# Led_Strip_8mm.net
KiCad netlist of a schematic drawn in Altium Designer
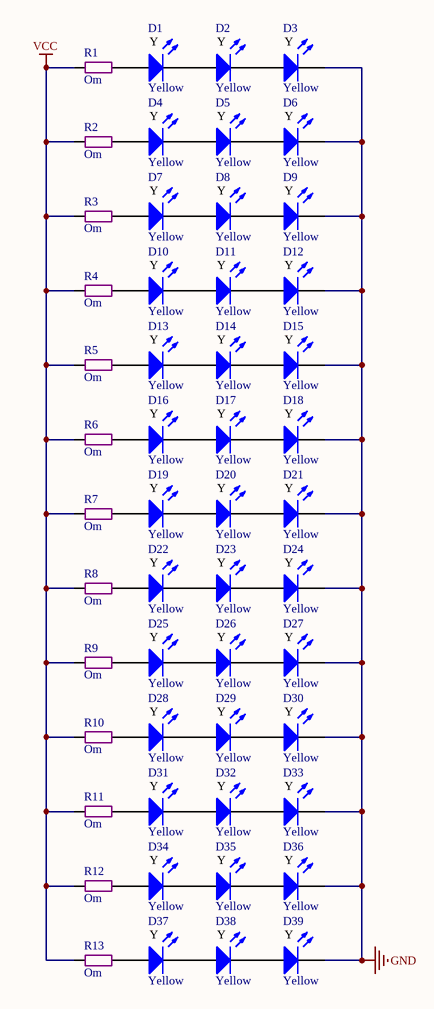
[diagram p0: Led Strip 8mm.SchDoc]

(export (version "E")
  (design (tool "Eeschema 10.0.6"))
  (components
    (comp (ref "D1")
      (value "Yellow")
      (footprint "LED:LED Round 8mm Yellow")
      (description "2.8-3v 25mA, 4-5cd")
      (libsource (lib "LED") (part "Led Round 8mm Yellow 0.5W"))
    )
    (comp (ref "D2")
      (value "Yellow")
      (footprint "LED:LED Round 8mm Yellow")
      (description "2.8-3v 25mA, 4-5cd")
      (libsource (lib "LED") (part "Led Round 8mm Yellow 0.5W"))
    )
    (comp (ref "D3")
      (value "Yellow")
      (footprint "LED:LED Round 8mm Yellow")
      (description "2.8-3v 25mA, 4-5cd")
      (libsource (lib "LED") (part "Led Round 8mm Yellow 0.5W"))
    )
    (comp (ref "D4")
      (value "Yellow")
      (footprint "LED:LED Round 8mm Yellow")
      (description "2.8-3v 25mA, 4-5cd")
      (libsource (lib "LED") (part "Led Round 8mm Yellow 0.5W"))
    )
    (comp (ref "D5")
      (value "Yellow")
      (footprint "LED:LED Round 8mm Yellow")
      (description "2.8-3v 25mA, 4-5cd")
      (libsource (lib "LED") (part "Led Round 8mm Yellow 0.5W"))
    )
    (comp (ref "D6")
      (value "Yellow")
      (footprint "LED:LED Round 8mm Yellow")
      (description "2.8-3v 25mA, 4-5cd")
      (libsource (lib "LED") (part "Led Round 8mm Yellow 0.5W"))
    )
    (comp (ref "D7")
      (value "Yellow")
      (footprint "LED:LED Round 8mm Yellow")
      (description "2.8-3v 25mA, 4-5cd")
      (libsource (lib "LED") (part "Led Round 8mm Yellow 0.5W"))
    )
    (comp (ref "D8")
      (value "Yellow")
      (footprint "LED:LED Round 8mm Yellow")
      (description "2.8-3v 25mA, 4-5cd")
      (libsource (lib "LED") (part "Led Round 8mm Yellow 0.5W"))
    )
    (comp (ref "D9")
      (value "Yellow")
      (footprint "LED:LED Round 8mm Yellow")
      (description "2.8-3v 25mA, 4-5cd")
      (libsource (lib "LED") (part "Led Round 8mm Yellow 0.5W"))
    )
    (comp (ref "D10")
      (value "Yellow")
      (footprint "LED:LED Round 8mm Yellow")
      (description "2.8-3v 25mA, 4-5cd")
      (libsource (lib "LED") (part "Led Round 8mm Yellow 0.5W"))
    )
    (comp (ref "D11")
      (value "Yellow")
      (footprint "LED:LED Round 8mm Yellow")
      (description "2.8-3v 25mA, 4-5cd")
      (libsource (lib "LED") (part "Led Round 8mm Yellow 0.5W"))
    )
    (comp (ref "D12")
      (value "Yellow")
      (footprint "LED:LED Round 8mm Yellow")
      (description "2.8-3v 25mA, 4-5cd")
      (libsource (lib "LED") (part "Led Round 8mm Yellow 0.5W"))
    )
    (comp (ref "D13")
      (value "Yellow")
      (footprint "LED:LED Round 8mm Yellow")
      (description "2.8-3v 25mA, 4-5cd")
      (libsource (lib "LED") (part "Led Round 8mm Yellow 0.5W"))
    )
    (comp (ref "D14")
      (value "Yellow")
      (footprint "LED:LED Round 8mm Yellow")
      (description "2.8-3v 25mA, 4-5cd")
      (libsource (lib "LED") (part "Led Round 8mm Yellow 0.5W"))
    )
    (comp (ref "D15")
      (value "Yellow")
      (footprint "LED:LED Round 8mm Yellow")
      (description "2.8-3v 25mA, 4-5cd")
      (libsource (lib "LED") (part "Led Round 8mm Yellow 0.5W"))
    )
    (comp (ref "D16")
      (value "Yellow")
      (footprint "LED:LED Round 8mm Yellow")
      (description "2.8-3v 25mA, 4-5cd")
      (libsource (lib "LED") (part "Led Round 8mm Yellow 0.5W"))
    )
    (comp (ref "D17")
      (value "Yellow")
      (footprint "LED:LED Round 8mm Yellow")
      (description "2.8-3v 25mA, 4-5cd")
      (libsource (lib "LED") (part "Led Round 8mm Yellow 0.5W"))
    )
    (comp (ref "D18")
      (value "Yellow")
      (footprint "LED:LED Round 8mm Yellow")
      (description "2.8-3v 25mA, 4-5cd")
      (libsource (lib "LED") (part "Led Round 8mm Yellow 0.5W"))
    )
    (comp (ref "D19")
      (value "Yellow")
      (footprint "LED:LED Round 8mm Yellow")
      (description "2.8-3v 25mA, 4-5cd")
      (libsource (lib "LED") (part "Led Round 8mm Yellow 0.5W"))
    )
    (comp (ref "D20")
      (value "Yellow")
      (footprint "LED:LED Round 8mm Yellow")
      (description "2.8-3v 25mA, 4-5cd")
      (libsource (lib "LED") (part "Led Round 8mm Yellow 0.5W"))
    )
    (comp (ref "D21")
      (value "Yellow")
      (footprint "LED:LED Round 8mm Yellow")
      (description "2.8-3v 25mA, 4-5cd")
      (libsource (lib "LED") (part "Led Round 8mm Yellow 0.5W"))
    )
    (comp (ref "D22")
      (value "Yellow")
      (footprint "LED:LED Round 8mm Yellow")
      (description "2.8-3v 25mA, 4-5cd")
      (libsource (lib "LED") (part "Led Round 8mm Yellow 0.5W"))
    )
    (comp (ref "D23")
      (value "Yellow")
      (footprint "LED:LED Round 8mm Yellow")
      (description "2.8-3v 25mA, 4-5cd")
      (libsource (lib "LED") (part "Led Round 8mm Yellow 0.5W"))
    )
    (comp (ref "D24")
      (value "Yellow")
      (footprint "LED:LED Round 8mm Yellow")
      (description "2.8-3v 25mA, 4-5cd")
      (libsource (lib "LED") (part "Led Round 8mm Yellow 0.5W"))
    )
    (comp (ref "D25")
      (value "Yellow")
      (footprint "LED:LED Round 8mm Yellow")
      (description "2.8-3v 25mA, 4-5cd")
      (libsource (lib "LED") (part "Led Round 8mm Yellow 0.5W"))
    )
    (comp (ref "D26")
      (value "Yellow")
      (footprint "LED:LED Round 8mm Yellow")
      (description "2.8-3v 25mA, 4-5cd")
      (libsource (lib "LED") (part "Led Round 8mm Yellow 0.5W"))
    )
    (comp (ref "D27")
      (value "Yellow")
      (footprint "LED:LED Round 8mm Yellow")
      (description "2.8-3v 25mA, 4-5cd")
      (libsource (lib "LED") (part "Led Round 8mm Yellow 0.5W"))
    )
    (comp (ref "D28")
      (value "Yellow")
      (footprint "LED:LED Round 8mm Yellow")
      (description "2.8-3v 25mA, 4-5cd")
      (libsource (lib "LED") (part "Led Round 8mm Yellow 0.5W"))
    )
    (comp (ref "D29")
      (value "Yellow")
      (footprint "LED:LED Round 8mm Yellow")
      (description "2.8-3v 25mA, 4-5cd")
      (libsource (lib "LED") (part "Led Round 8mm Yellow 0.5W"))
    )
    (comp (ref "D30")
      (value "Yellow")
      (footprint "LED:LED Round 8mm Yellow")
      (description "2.8-3v 25mA, 4-5cd")
      (libsource (lib "LED") (part "Led Round 8mm Yellow 0.5W"))
    )
    (comp (ref "D31")
      (value "Yellow")
      (footprint "LED:LED Round 8mm Yellow")
      (description "2.8-3v 25mA, 4-5cd")
      (libsource (lib "LED") (part "Led Round 8mm Yellow 0.5W"))
    )
    (comp (ref "D32")
      (value "Yellow")
      (footprint "LED:LED Round 8mm Yellow")
      (description "2.8-3v 25mA, 4-5cd")
      (libsource (lib "LED") (part "Led Round 8mm Yellow 0.5W"))
    )
    (comp (ref "D33")
      (value "Yellow")
      (footprint "LED:LED Round 8mm Yellow")
      (description "2.8-3v 25mA, 4-5cd")
      (libsource (lib "LED") (part "Led Round 8mm Yellow 0.5W"))
    )
    (comp (ref "D34")
      (value "Yellow")
      (footprint "LED:LED Round 8mm Yellow")
      (description "2.8-3v 25mA, 4-5cd")
      (libsource (lib "LED") (part "Led Round 8mm Yellow 0.5W"))
    )
    (comp (ref "D35")
      (value "Yellow")
      (footprint "LED:LED Round 8mm Yellow")
      (description "2.8-3v 25mA, 4-5cd")
      (libsource (lib "LED") (part "Led Round 8mm Yellow 0.5W"))
    )
    (comp (ref "D36")
      (value "Yellow")
      (footprint "LED:LED Round 8mm Yellow")
      (description "2.8-3v 25mA, 4-5cd")
      (libsource (lib "LED") (part "Led Round 8mm Yellow 0.5W"))
    )
    (comp (ref "D37")
      (value "Yellow")
      (footprint "LED:LED Round 8mm Yellow")
      (description "2.8-3v 25mA, 4-5cd")
      (libsource (lib "LED") (part "Led Round 8mm Yellow 0.5W"))
    )
    (comp (ref "D38")
      (value "Yellow")
      (footprint "LED:LED Round 8mm Yellow")
      (description "2.8-3v 25mA, 4-5cd")
      (libsource (lib "LED") (part "Led Round 8mm Yellow 0.5W"))
    )
    (comp (ref "D39")
      (value "Yellow")
      (footprint "LED:LED Round 8mm Yellow")
      (description "2.8-3v 25mA, 4-5cd")
      (libsource (lib "LED") (part "Led Round 8mm Yellow 0.5W"))
    )
    (comp (ref "R1")
      (value "Om")
      (footprint "PassiveComponents:Res p20.32 (9p) 2w")
      (description "5W Cement")
      (libsource (lib "PassiveComponents") (part "Res 2W"))
    )
    (comp (ref "R2")
      (value "Om")
      (footprint "PassiveComponents:Res p20.32 (9p) 2w")
      (description "5W Cement")
      (libsource (lib "PassiveComponents") (part "Res 2W"))
    )
    (comp (ref "R3")
      (value "Om")
      (footprint "PassiveComponents:Res p20.32 (9p) 2w")
      (description "5W Cement")
      (libsource (lib "PassiveComponents") (part "Res 2W"))
    )
    (comp (ref "R4")
      (value "Om")
      (footprint "PassiveComponents:Res p20.32 (9p) 2w")
      (description "5W Cement")
      (libsource (lib "PassiveComponents") (part "Res 2W"))
    )
    (comp (ref "R5")
      (value "Om")
      (footprint "PassiveComponents:Res p20.32 (9p) 2w")
      (description "5W Cement")
      (libsource (lib "PassiveComponents") (part "Res 2W"))
    )
    (comp (ref "R6")
      (value "Om")
      (footprint "PassiveComponents:Res p20.32 (9p) 2w")
      (description "5W Cement")
      (libsource (lib "PassiveComponents") (part "Res 2W"))
    )
    (comp (ref "R7")
      (value "Om")
      (footprint "PassiveComponents:Res p20.32 (9p) 2w")
      (description "5W Cement")
      (libsource (lib "PassiveComponents") (part "Res 2W"))
    )
    (comp (ref "R8")
      (value "Om")
      (footprint "PassiveComponents:Res p20.32 (9p) 2w")
      (description "5W Cement")
      (libsource (lib "PassiveComponents") (part "Res 2W"))
    )
    (comp (ref "R9")
      (value "Om")
      (footprint "PassiveComponents:Res p20.32 (9p) 2w")
      (description "5W Cement")
      (libsource (lib "PassiveComponents") (part "Res 2W"))
    )
    (comp (ref "R10")
      (value "Om")
      (footprint "PassiveComponents:Res p20.32 (9p) 2w")
      (description "5W Cement")
      (libsource (lib "PassiveComponents") (part "Res 2W"))
    )
    (comp (ref "R11")
      (value "Om")
      (footprint "PassiveComponents:Res p20.32 (9p) 2w")
      (description "5W Cement")
      (libsource (lib "PassiveComponents") (part "Res 2W"))
    )
    (comp (ref "R12")
      (value "Om")
      (footprint "PassiveComponents:Res p20.32 (9p) 2w")
      (description "5W Cement")
      (libsource (lib "PassiveComponents") (part "Res 2W"))
    )
    (comp (ref "R13")
      (value "Om")
      (footprint "PassiveComponents:Res p20.32 (9p) 2w")
      (description "5W Cement")
      (libsource (lib "PassiveComponents") (part "Res 2W"))
    )
  )
  (nets
    (net (code "1") (name "GND") (class "Default")
      (node (ref "D12") (pin "K") (pinfunction "K_K") (pintype "passive"))
      (node (ref "D15") (pin "K") (pinfunction "K_K") (pintype "passive"))
      (node (ref "D18") (pin "K") (pinfunction "K_K") (pintype "passive"))
      (node (ref "D21") (pin "K") (pinfunction "K_K") (pintype "passive"))
      (node (ref "D24") (pin "K") (pinfunction "K_K") (pintype "passive"))
      (node (ref "D27") (pin "K") (pinfunction "K_K") (pintype "passive"))
      (node (ref "D3") (pin "K") (pinfunction "K_K") (pintype "passive"))
      (node (ref "D30") (pin "K") (pinfunction "K_K") (pintype "passive"))
      (node (ref "D33") (pin "K") (pinfunction "K_K") (pintype "passive"))
      (node (ref "D36") (pin "K") (pinfunction "K_K") (pintype "passive"))
      (node (ref "D39") (pin "K") (pinfunction "K_K") (pintype "passive"))
      (node (ref "D6") (pin "K") (pinfunction "K_K") (pintype "passive"))
      (node (ref "D9") (pin "K") (pinfunction "K_K") (pintype "passive"))
    )
    (net (code "2") (name "Net-(D1-PadA)") (class "Default")
      (node (ref "D1") (pin "A") (pinfunction "A_A") (pintype "passive"))
      (node (ref "R1") (pin "2") (pinfunction "2_2") (pintype "passive"))
    )
    (net (code "3") (name "Net-(D1-PadK)") (class "Default")
      (node (ref "D1") (pin "K") (pinfunction "K_K") (pintype "passive"))
      (node (ref "D2") (pin "A") (pinfunction "A_A") (pintype "passive"))
    )
    (net (code "4") (name "Net-(D2-PadK)") (class "Default")
      (node (ref "D2") (pin "K") (pinfunction "K_K") (pintype "passive"))
      (node (ref "D3") (pin "A") (pinfunction "A_A") (pintype "passive"))
    )
    (net (code "5") (name "Net-(D4-PadA)") (class "Default")
      (node (ref "D4") (pin "A") (pinfunction "A_A") (pintype "passive"))
      (node (ref "R2") (pin "2") (pinfunction "2_2") (pintype "passive"))
    )
    (net (code "6") (name "Net-(D4-PadK)") (class "Default")
      (node (ref "D4") (pin "K") (pinfunction "K_K") (pintype "passive"))
      (node (ref "D5") (pin "A") (pinfunction "A_A") (pintype "passive"))
    )
    (net (code "7") (name "Net-(D5-PadK)") (class "Default")
      (node (ref "D5") (pin "K") (pinfunction "K_K") (pintype "passive"))
      (node (ref "D6") (pin "A") (pinfunction "A_A") (pintype "passive"))
    )
    (net (code "8") (name "Net-(D7-PadA)") (class "Default")
      (node (ref "D7") (pin "A") (pinfunction "A_A") (pintype "passive"))
      (node (ref "R3") (pin "2") (pinfunction "2_2") (pintype "passive"))
    )
    (net (code "9") (name "Net-(D7-PadK)") (class "Default")
      (node (ref "D7") (pin "K") (pinfunction "K_K") (pintype "passive"))
      (node (ref "D8") (pin "A") (pinfunction "A_A") (pintype "passive"))
    )
    (net (code "10") (name "Net-(D8-PadK)") (class "Default")
      (node (ref "D8") (pin "K") (pinfunction "K_K") (pintype "passive"))
      (node (ref "D9") (pin "A") (pinfunction "A_A") (pintype "passive"))
    )
    (net (code "11") (name "Net-(D10-PadA)") (class "Default")
      (node (ref "D10") (pin "A") (pinfunction "A_A") (pintype "passive"))
      (node (ref "R4") (pin "2") (pinfunction "2_2") (pintype "passive"))
    )
    (net (code "12") (name "Net-(D10-PadK)") (class "Default")
      (node (ref "D10") (pin "K") (pinfunction "K_K") (pintype "passive"))
      (node (ref "D11") (pin "A") (pinfunction "A_A") (pintype "passive"))
    )
    (net (code "13") (name "Net-(D11-PadK)") (class "Default")
      (node (ref "D11") (pin "K") (pinfunction "K_K") (pintype "passive"))
      (node (ref "D12") (pin "A") (pinfunction "A_A") (pintype "passive"))
    )
    (net (code "14") (name "Net-(D13-PadA)") (class "Default")
      (node (ref "D13") (pin "A") (pinfunction "A_A") (pintype "passive"))
      (node (ref "R5") (pin "2") (pinfunction "2_2") (pintype "passive"))
    )
    (net (code "15") (name "Net-(D13-PadK)") (class "Default")
      (node (ref "D13") (pin "K") (pinfunction "K_K") (pintype "passive"))
      (node (ref "D14") (pin "A") (pinfunction "A_A") (pintype "passive"))
    )
    (net (code "16") (name "Net-(D14-PadK)") (class "Default")
      (node (ref "D14") (pin "K") (pinfunction "K_K") (pintype "passive"))
      (node (ref "D15") (pin "A") (pinfunction "A_A") (pintype "passive"))
    )
    (net (code "17") (name "Net-(D16-PadA)") (class "Default")
      (node (ref "D16") (pin "A") (pinfunction "A_A") (pintype "passive"))
      (node (ref "R6") (pin "2") (pinfunction "2_2") (pintype "passive"))
    )
    (net (code "18") (name "Net-(D16-PadK)") (class "Default")
      (node (ref "D16") (pin "K") (pinfunction "K_K") (pintype "passive"))
      (node (ref "D17") (pin "A") (pinfunction "A_A") (pintype "passive"))
    )
    (net (code "19") (name "Net-(D17-PadK)") (class "Default")
      (node (ref "D17") (pin "K") (pinfunction "K_K") (pintype "passive"))
      (node (ref "D18") (pin "A") (pinfunction "A_A") (pintype "passive"))
    )
    (net (code "20") (name "Net-(D19-PadA)") (class "Default")
      (node (ref "D19") (pin "A") (pinfunction "A_A") (pintype "passive"))
      (node (ref "R7") (pin "2") (pinfunction "2_2") (pintype "passive"))
    )
    (net (code "21") (name "Net-(D19-PadK)") (class "Default")
      (node (ref "D19") (pin "K") (pinfunction "K_K") (pintype "passive"))
      (node (ref "D20") (pin "A") (pinfunction "A_A") (pintype "passive"))
    )
    (net (code "22") (name "Net-(D20-PadK)") (class "Default")
      (node (ref "D20") (pin "K") (pinfunction "K_K") (pintype "passive"))
      (node (ref "D21") (pin "A") (pinfunction "A_A") (pintype "passive"))
    )
    (net (code "23") (name "Net-(D22-PadA)") (class "Default")
      (node (ref "D22") (pin "A") (pinfunction "A_A") (pintype "passive"))
      (node (ref "R8") (pin "2") (pinfunction "2_2") (pintype "passive"))
    )
    (net (code "24") (name "Net-(D22-PadK)") (class "Default")
      (node (ref "D22") (pin "K") (pinfunction "K_K") (pintype "passive"))
      (node (ref "D23") (pin "A") (pinfunction "A_A") (pintype "passive"))
    )
    (net (code "25") (name "Net-(D23-PadK)") (class "Default")
      (node (ref "D23") (pin "K") (pinfunction "K_K") (pintype "passive"))
      (node (ref "D24") (pin "A") (pinfunction "A_A") (pintype "passive"))
    )
    (net (code "26") (name "Net-(D25-PadA)") (class "Default")
      (node (ref "D25") (pin "A") (pinfunction "A_A") (pintype "passive"))
      (node (ref "R9") (pin "2") (pinfunction "2_2") (pintype "passive"))
    )
    (net (code "27") (name "Net-(D25-PadK)") (class "Default")
      (node (ref "D25") (pin "K") (pinfunction "K_K") (pintype "passive"))
      (node (ref "D26") (pin "A") (pinfunction "A_A") (pintype "passive"))
    )
    (net (code "28") (name "Net-(D26-PadK)") (class "Default")
      (node (ref "D26") (pin "K") (pinfunction "K_K") (pintype "passive"))
      (node (ref "D27") (pin "A") (pinfunction "A_A") (pintype "passive"))
    )
    (net (code "29") (name "Net-(D28-PadA)") (class "Default")
      (node (ref "D28") (pin "A") (pinfunction "A_A") (pintype "passive"))
      (node (ref "R10") (pin "2") (pinfunction "2_2") (pintype "passive"))
    )
    (net (code "30") (name "Net-(D28-PadK)") (class "Default")
      (node (ref "D28") (pin "K") (pinfunction "K_K") (pintype "passive"))
      (node (ref "D29") (pin "A") (pinfunction "A_A") (pintype "passive"))
    )
    (net (code "31") (name "Net-(D29-PadK)") (class "Default")
      (node (ref "D29") (pin "K") (pinfunction "K_K") (pintype "passive"))
      (node (ref "D30") (pin "A") (pinfunction "A_A") (pintype "passive"))
    )
    (net (code "32") (name "Net-(D31-PadA)") (class "Default")
      (node (ref "D31") (pin "A") (pinfunction "A_A") (pintype "passive"))
      (node (ref "R11") (pin "2") (pinfunction "2_2") (pintype "passive"))
    )
    (net (code "33") (name "Net-(D31-PadK)") (class "Default")
      (node (ref "D31") (pin "K") (pinfunction "K_K") (pintype "passive"))
      (node (ref "D32") (pin "A") (pinfunction "A_A") (pintype "passive"))
    )
    (net (code "34") (name "Net-(D32-PadK)") (class "Default")
      (node (ref "D32") (pin "K") (pinfunction "K_K") (pintype "passive"))
      (node (ref "D33") (pin "A") (pinfunction "A_A") (pintype "passive"))
    )
    (net (code "35") (name "Net-(D34-PadA)") (class "Default")
      (node (ref "D34") (pin "A") (pinfunction "A_A") (pintype "passive"))
      (node (ref "R12") (pin "2") (pinfunction "2_2") (pintype "passive"))
    )
    (net (code "36") (name "Net-(D34-PadK)") (class "Default")
      (node (ref "D34") (pin "K") (pinfunction "K_K") (pintype "passive"))
      (node (ref "D35") (pin "A") (pinfunction "A_A") (pintype "passive"))
    )
    (net (code "37") (name "Net-(D35-PadK)") (class "Default")
      (node (ref "D35") (pin "K") (pinfunction "K_K") (pintype "passive"))
      (node (ref "D36") (pin "A") (pinfunction "A_A") (pintype "passive"))
    )
    (net (code "38") (name "Net-(D37-PadA)") (class "Default")
      (node (ref "D37") (pin "A") (pinfunction "A_A") (pintype "passive"))
      (node (ref "R13") (pin "2") (pinfunction "2_2") (pintype "passive"))
    )
    (net (code "39") (name "Net-(D37-PadK)") (class "Default")
      (node (ref "D37") (pin "K") (pinfunction "K_K") (pintype "passive"))
      (node (ref "D38") (pin "A") (pinfunction "A_A") (pintype "passive"))
    )
    (net (code "40") (name "Net-(D38-PadK)") (class "Default")
      (node (ref "D38") (pin "K") (pinfunction "K_K") (pintype "passive"))
      (node (ref "D39") (pin "A") (pinfunction "A_A") (pintype "passive"))
    )
    (net (code "41") (name "VCC") (class "Default")
      (node (ref "R1") (pin "1") (pinfunction "1_1") (pintype "passive"))
      (node (ref "R10") (pin "1") (pinfunction "1_1") (pintype "passive"))
      (node (ref "R11") (pin "1") (pinfunction "1_1") (pintype "passive"))
      (node (ref "R12") (pin "1") (pinfunction "1_1") (pintype "passive"))
      (node (ref "R13") (pin "1") (pinfunction "1_1") (pintype "passive"))
      (node (ref "R2") (pin "1") (pinfunction "1_1") (pintype "passive"))
      (node (ref "R3") (pin "1") (pinfunction "1_1") (pintype "passive"))
      (node (ref "R4") (pin "1") (pinfunction "1_1") (pintype "passive"))
      (node (ref "R5") (pin "1") (pinfunction "1_1") (pintype "passive"))
      (node (ref "R6") (pin "1") (pinfunction "1_1") (pintype "passive"))
      (node (ref "R7") (pin "1") (pinfunction "1_1") (pintype "passive"))
      (node (ref "R8") (pin "1") (pinfunction "1_1") (pintype "passive"))
      (node (ref "R9") (pin "1") (pinfunction "1_1") (pintype "passive"))
    )
  )
)
